# MCU.net
KiCad netlist of a schematic drawn in Altium Designer
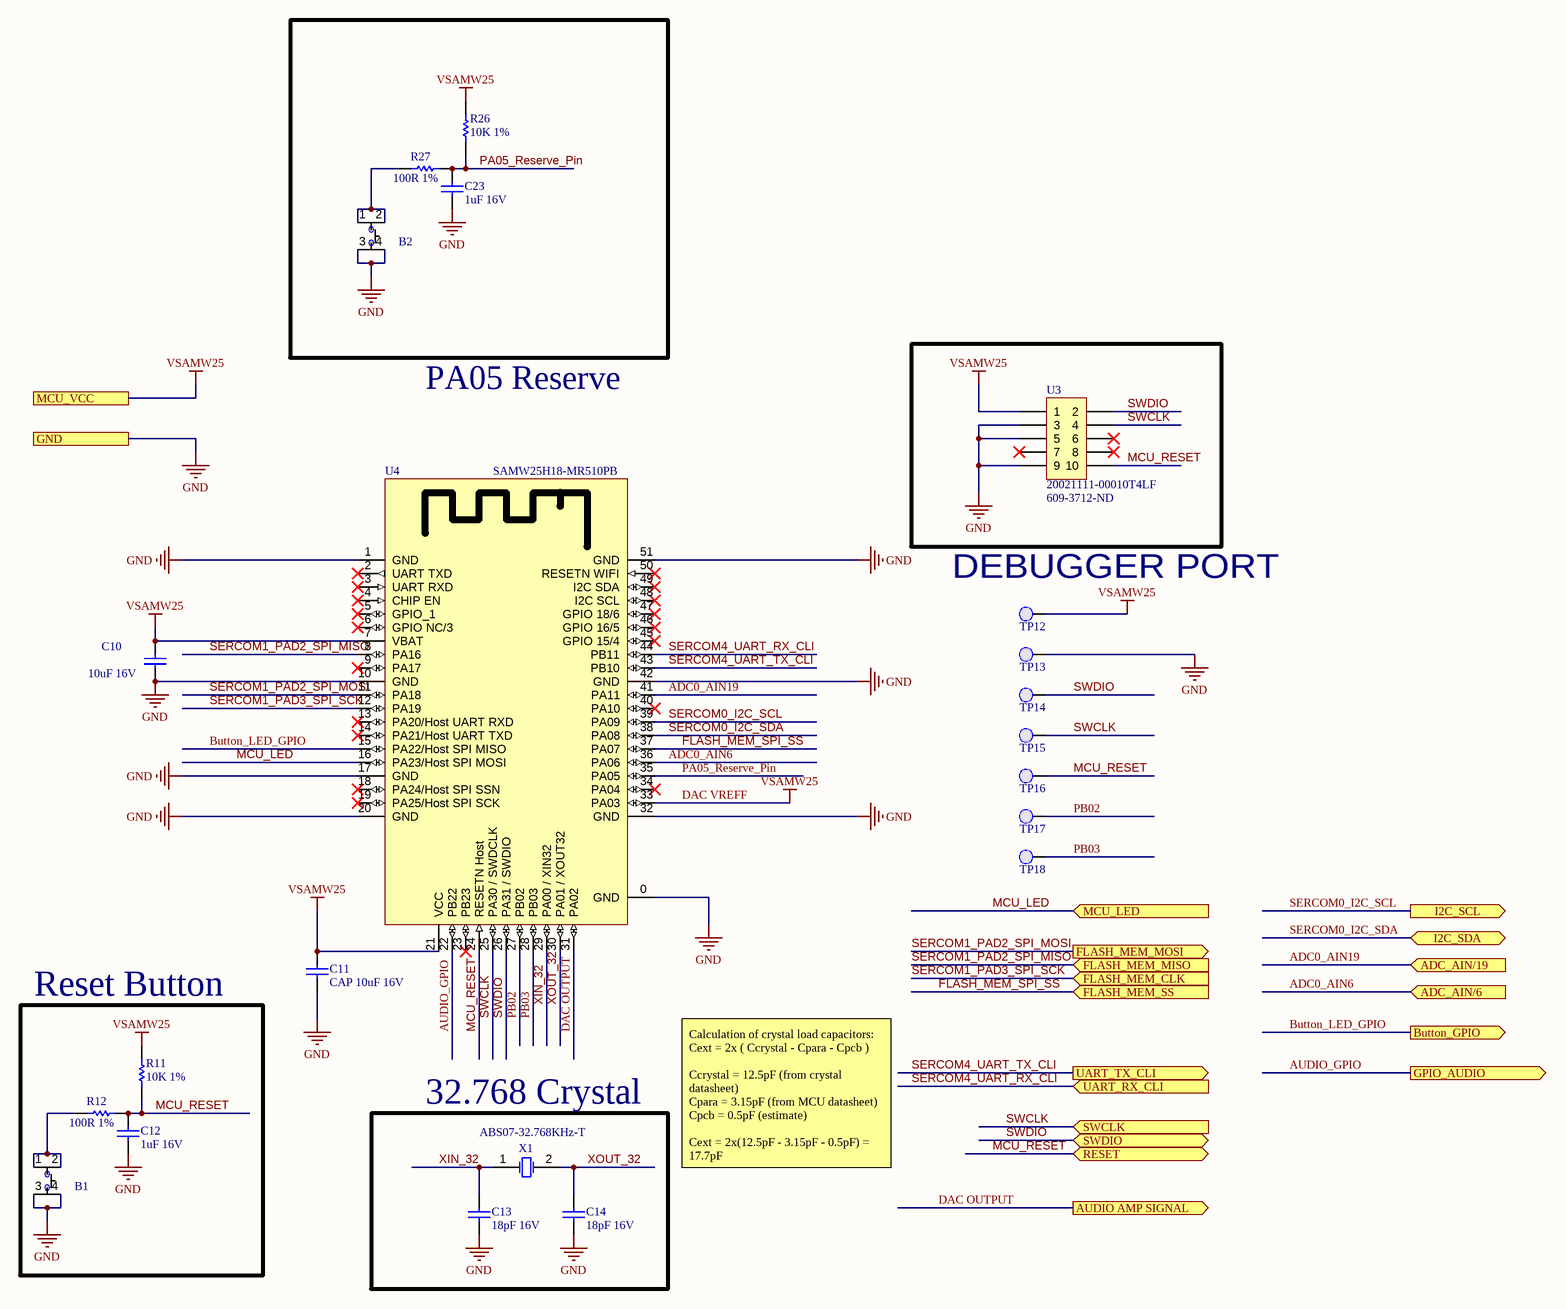
[diagram p0: MCU.SchDoc]

(export (version "E")
  (design (tool "Eeschema 10.0.6"))
  (components
    (comp (ref "B1")
      (value "PTS810 SJK 250 SMTR LFS")
      (footprint "PTS810 SJK 250 SMTR LFS")
      (description "SWITCH TACTILE SPST-NO 0.05A 16V Tactile Switch SPST-NO Top Actuated Surface Mount")
      (fields
        (field (name "MANUFACTURER") "ITT /  C&K Components")
        (field (name "MANUFACTURER PART NUMBER") "PTS810SJK250SMTRLFS")
      )
      (libsource (lib "Schematics") (part "PTS810 SJK 250 SMTR LFS"))
    )
    (comp (ref "B2")
      (value "PTS810 SJK 250 SMTR LFS")
      (footprint "PTS810 SJK 250 SMTR LFS")
      (description "SWITCH TACTILE SPST-NO 0.05A 16V Tactile Switch SPST-NO Top Actuated Surface Mount")
      (fields
        (field (name "MANUFACTURER") "ITT /  C&K Components")
        (field (name "MANUFACTURER PART NUMBER") "PTS810SJK250SMTRLFS")
      )
      (libsource (lib "Schematics") (part "PTS810 SJK 250 SMTR LFS"))
    )
    (comp (ref "C10")
      (value "10uF 16V")
      (footprint "CAPC0805(2012)145_N")
      (description "CAP 10uF 16V ±10% 0805 (2012 Metric) Thickness 1.45mm SMD")
      (fields (field (name "TOLERANCE") "Â±10%"))
      (libsource (lib "Altium Content Vault") (part "CAP"))
    )
    (comp (ref "C11")
      (value "CAP 10uF 16V")
      (footprint "CAPC0805(2012)145_N")
      (description "CAP 10uF 16V ±10% 0805 (2012 Metric) Thickness 1.45mm SMD")
      (fields (field (name "TOLERANCE") "Â±10%"))
      (libsource (lib "Altium Content Vault") (part "CAP"))
    )
    (comp (ref "C12")
      (value "1uF 16V")
      (footprint "CAPC0603(1608)100_N")
      (description "CAP 1uF 16V ±5% 0603 (1608 Metric) Thickness 1mm SMD")
      (fields (field (name "TOLERANCE") "Â±5%"))
      (libsource (lib "Altium Content Vault") (part "CAP"))
    )
    (comp (ref "C13")
      (value "18pF 16V")
      (footprint "CAPC0603(1608)100_N")
      (description "CAP 18pF 16V ±5% 0603 (1608 Metric) Thickness 1mm SMD")
      (fields (field (name "TOLERANCE") "Â±5%"))
      (libsource (lib "Altium Content Vault") (part "CAP"))
    )
    (comp (ref "C14")
      (value "18pF 16V")
      (footprint "CAPC0603(1608)100_N")
      (description "CAP 18pF 16V ±5% 0603 (1608 Metric) Thickness 1mm SMD")
      (fields (field (name "TOLERANCE") "Â±5%"))
      (libsource (lib "Altium Content Vault") (part "CAP"))
    )
    (comp (ref "C23")
      (value "1uF 16V")
      (footprint "CAPC0603(1608)100_N")
      (description "CAP 1uF 16V ±5% 0603 (1608 Metric) Thickness 1mm SMD")
      (fields (field (name "TOLERANCE") "Â±5%"))
      (libsource (lib "Altium Content Vault") (part "CAP"))
    )
    (comp (ref "R11")
      (value "10K 1%")
      (footprint "RESC0603(1608)_N")
      (description "10K 0.1W 1% 0603 (1608 Metric)  SMD")
      (fields (field (name "POWER") "0.1 W") (field (name "TOLERANCE") "1 %"))
      (libsource (lib "Altium Content Vault") (part "RES"))
    )
    (comp (ref "R12")
      (value "100R 1%")
      (footprint "RESC0603(1608)_N")
      (description "100R 0.1W 1% 0603 (1608 Metric)  SMD")
      (fields (field (name "TOLERANCE") "1 %") (field (name "POWER") "0.1 W"))
      (libsource (lib "Altium Content Vault") (part "RES"))
    )
    (comp (ref "R26")
      (value "10K 1%")
      (footprint "RESC0603(1608)_N")
      (description "10K 0.1W 1% 0603 (1608 Metric)  SMD")
      (fields (field (name "POWER") "0.1 W") (field (name "TOLERANCE") "1 %"))
      (libsource (lib "Altium Content Vault") (part "RES"))
    )
    (comp (ref "R27")
      (value "100R 1%")
      (footprint "RESC0603(1608)_N")
      (description "100R 0.1W 1% 0603 (1608 Metric)  SMD")
      (fields (field (name "TOLERANCE") "1 %") (field (name "POWER") "0.1 W"))
      (libsource (lib "Altium Content Vault") (part "RES"))
    )
    (comp (ref "TP12")
      (value "0.1\" Pad")
      (footprint "PCBComponent")
      (libsource (lib "Components - 12.02.20 - 18.05") (part "0.1{dblquote} Pad-A.4"))
    )
    (comp (ref "TP13")
      (value "0.1\" Pad")
      (footprint "PCBComponent")
      (libsource (lib "Components - 12.02.20 - 18.05") (part "0.1{dblquote} Pad-A.4"))
    )
    (comp (ref "TP14")
      (value "0.1\" Pad")
      (footprint "PCBComponent")
      (libsource (lib "Components - 12.02.20 - 18.05") (part "0.1{dblquote} Pad-A.4"))
    )
    (comp (ref "TP15")
      (value "0.1\" Pad")
      (footprint "PCBComponent")
      (libsource (lib "Components - 12.02.20 - 18.05") (part "0.1{dblquote} Pad-A.4"))
    )
    (comp (ref "TP16")
      (value "0.1\" Pad")
      (footprint "PCBComponent")
      (libsource (lib "Components - 12.02.20 - 18.05") (part "0.1{dblquote} Pad-A.4"))
    )
    (comp (ref "TP17")
      (value "0.1\" Pad")
      (footprint "PCBComponent")
      (libsource (lib "Components - 12.02.20 - 18.05") (part "0.1{dblquote} Pad-A.4"))
    )
    (comp (ref "TP18")
      (value "0.1\" Pad")
      (footprint "PCBComponent")
      (libsource (lib "Components - 12.02.20 - 18.05") (part "0.1{dblquote} Pad-A.4"))
    )
    (comp (ref "U3")
      (value "20021111-00010T4LF")
      (footprint "20021111-00010T4LF")
      (description "CONN HEADER 10POS UNSHD VERT T/H")
      (fields
        (field (name "MANUFACTURER") "Amphenol / FCI")
        (field (name "SUPPLIER PART NUMBER 1") "609-3712-ND")
      )
      (libsource (lib "Schematics") (part "20021111-00010T4LF"))
    )
    (comp (ref "U4")
      (value "SAMW25H18-MR510PB")
      (footprint "SAMW25H18-MR510PB")
      (description "RF TXRX MODULE WIFI TRACE ANT")
      (fields
        (field (name "MANUFACTURER") "Atmel")
        (field (name "MANUFACTURER PART NUMBER") "ATSAMW25H18-MR510PB")
      )
      (libsource (lib "Schematics") (part "SAMW25H18-MR510PB"))
    )
    (comp (ref "X1")
      (value "ABS07-32.768KHz-T")
      (footprint "ABRA-ABS07-2_V")
      (description "Crystal, 32.768 kHz, 12.5 pF, -40 to 85 degC, SMD Low Profile 3.2 x 1.5 x 0.9 mm, Tape and Reel")
      (fields (field (name "MANUFACTURER") "Abracon"))
      (libsource (lib "Altium Content Vault") (part "ABRA-ABS07-2"))
    )
  )
  (nets
    (net (code "1") (name "/ADC0_AIN6") (class "Default")
      (node (ref "U4") (pin "36") (pinfunction "PA06_36") (pintype "bidirectional"))
    )
    (net (code "2") (name "/ADC0_AIN19") (class "Default")
      (node (ref "U4") (pin "41") (pinfunction "PA11_41") (pintype "bidirectional"))
    )
    (net (code "3") (name "/AUDIO_GPIO") (class "Default")
      (node (ref "U4") (pin "22") (pinfunction "PB22_22") (pintype "bidirectional"))
    )
    (net (code "4") (name "/Button_LED_GPIO") (class "Default")
      (node (ref "U4") (pin "15") (pinfunction "PA22/Host_SPI_MISO_15") (pintype "bidirectional"))
    )
    (net (code "5") (name "/DAC OUTPUT") (class "Default")
      (node (ref "U4") (pin "31") (pinfunction "PA02_31") (pintype "bidirectional"))
    )
    (net (code "6") (name "/FLASH_MEM_SPI_SS") (class "Default")
      (node (ref "U4") (pin "37") (pinfunction "PA07_37") (pintype "bidirectional"))
    )
    (net (code "7") (name "/MCU_LED") (class "Default")
      (node (ref "U4") (pin "16") (pinfunction "PA23/Host_SPI_MOSI_16") (pintype "bidirectional"))
    )
    (net (code "8") (name "/MCU_RESET") (class "Default")
      (node (ref "C12") (pin "2") (pinfunction "2_2") (pintype "passive"))
      (node (ref "R11") (pin "1") (pinfunction "1_1") (pintype "passive"))
      (node (ref "R12") (pin "2") (pinfunction "2_2") (pintype "passive"))
      (node (ref "TP16") (pin "1") (pinfunction "PAD_1") (pintype "passive"))
      (node (ref "U3") (pin "10") (pinfunction "10_10") (pintype "passive"))
      (node (ref "U4") (pin "24") (pinfunction "RESETN_Host_24") (pintype "input"))
    )
    (net (code "9") (name "/PA05_Reserve_Pin") (class "Default")
      (node (ref "C23") (pin "2") (pinfunction "2_2") (pintype "passive"))
      (node (ref "R26") (pin "1") (pinfunction "1_1") (pintype "passive"))
      (node (ref "R27") (pin "2") (pinfunction "2_2") (pintype "passive"))
      (node (ref "U4") (pin "35") (pinfunction "PA05_35") (pintype "bidirectional"))
    )
    (net (code "10") (name "/PB02") (class "Default")
      (node (ref "TP17") (pin "1") (pinfunction "PAD_1") (pintype "passive"))
      (node (ref "U4") (pin "27") (pinfunction "PB02_27") (pintype "bidirectional"))
    )
    (net (code "11") (name "/PB03") (class "Default")
      (node (ref "TP18") (pin "1") (pinfunction "PAD_1") (pintype "passive"))
      (node (ref "U4") (pin "28") (pinfunction "PB03_28") (pintype "bidirectional"))
    )
    (net (code "12") (name "/SERCOM0_I2C_SCL") (class "Default")
      (node (ref "U4") (pin "39") (pinfunction "PA09_39") (pintype "bidirectional"))
    )
    (net (code "13") (name "/SERCOM0_I2C_SDA") (class "Default")
      (node (ref "U4") (pin "38") (pinfunction "PA08_38") (pintype "bidirectional"))
    )
    (net (code "14") (name "/SERCOM1_PAD2_SPI_MISO") (class "Default")
      (node (ref "U4") (pin "8") (pinfunction "PA16_8") (pintype "bidirectional"))
    )
    (net (code "15") (name "/SERCOM1_PAD2_SPI_MOSI") (class "Default")
      (node (ref "U4") (pin "11") (pinfunction "PA18_11") (pintype "bidirectional"))
    )
    (net (code "16") (name "/SERCOM1_PAD3_SPI_SCK") (class "Default")
      (node (ref "U4") (pin "12") (pinfunction "PA19_12") (pintype "bidirectional"))
    )
    (net (code "17") (name "/SERCOM4_UART_RX_CLI") (class "Default")
      (node (ref "U4") (pin "44") (pinfunction "PB11_44") (pintype "bidirectional"))
    )
    (net (code "18") (name "/SERCOM4_UART_TX_CLI") (class "Default")
      (node (ref "U4") (pin "43") (pinfunction "PB10_43") (pintype "bidirectional"))
    )
    (net (code "19") (name "/SWCLK") (class "Default")
      (node (ref "TP15") (pin "1") (pinfunction "PAD_1") (pintype "passive"))
      (node (ref "U3") (pin "4") (pinfunction "4_4") (pintype "passive"))
      (node (ref "U4") (pin "25") (pinfunction "PA30_/_SWDCLK_25") (pintype "bidirectional"))
    )
    (net (code "20") (name "/SWDIO") (class "Default")
      (node (ref "TP14") (pin "1") (pinfunction "PAD_1") (pintype "passive"))
      (node (ref "U3") (pin "2") (pinfunction "2_2") (pintype "passive"))
      (node (ref "U4") (pin "26") (pinfunction "PA31_/_SWDIO_26") (pintype "bidirectional"))
    )
    (net (code "21") (name "/XIN_32") (class "Default")
      (node (ref "C13") (pin "2") (pinfunction "2_2") (pintype "passive"))
      (node (ref "U4") (pin "29") (pinfunction "PA00_/_XIN32_29") (pintype "bidirectional"))
      (node (ref "X1") (pin "1") (pinfunction "X1_1") (pintype "passive"))
    )
    (net (code "22") (name "/XOUT_32") (class "Default")
      (node (ref "C14") (pin "2") (pinfunction "2_2") (pintype "passive"))
      (node (ref "U4") (pin "30") (pinfunction "PA01_/_XOUT32_30") (pintype "bidirectional"))
      (node (ref "X1") (pin "2") (pinfunction "X2_2") (pintype "passive"))
    )
    (net (code "23") (name "GND") (class "Default")
      (node (ref "B1") (pin "3") (pinfunction "3_3") (pintype "power_in"))
      (node (ref "B1") (pin "4") (pinfunction "4_4") (pintype "power_in"))
      (node (ref "B2") (pin "3") (pinfunction "3_3") (pintype "power_in"))
      (node (ref "B2") (pin "4") (pinfunction "4_4") (pintype "power_in"))
      (node (ref "C10") (pin "1") (pinfunction "1_1") (pintype "passive"))
      (node (ref "C11") (pin "1") (pinfunction "1_1") (pintype "passive"))
      (node (ref "C12") (pin "1") (pinfunction "1_1") (pintype "passive"))
      (node (ref "C13") (pin "1") (pinfunction "1_1") (pintype "passive"))
      (node (ref "C14") (pin "1") (pinfunction "1_1") (pintype "passive"))
      (node (ref "C23") (pin "1") (pinfunction "1_1") (pintype "passive"))
      (node (ref "TP13") (pin "1") (pinfunction "PAD_1") (pintype "passive"))
      (node (ref "U3") (pin "3") (pinfunction "3_3") (pintype "passive"))
      (node (ref "U3") (pin "5") (pinfunction "5_5") (pintype "passive"))
      (node (ref "U3") (pin "9") (pinfunction "9_9") (pintype "passive"))
      (node (ref "U4") (pin "0") (pinfunction "GND_0") (pintype "power_in"))
      (node (ref "U4") (pin "1") (pinfunction "GND_1") (pintype "power_in"))
      (node (ref "U4") (pin "10") (pinfunction "GND_10") (pintype "power_in"))
      (node (ref "U4") (pin "17") (pinfunction "GND_17") (pintype "power_in"))
      (node (ref "U4") (pin "20") (pinfunction "GND_20") (pintype "power_in"))
      (node (ref "U4") (pin "32") (pinfunction "GND_32") (pintype "power_in"))
      (node (ref "U4") (pin "42") (pinfunction "GND_42") (pintype "power_in"))
      (node (ref "U4") (pin "51") (pinfunction "GND_51") (pintype "power_in"))
    )
    (net (code "24") (name "Net-(B1-Pad1)") (class "Default")
      (node (ref "B1") (pin "1") (pinfunction "1_1") (pintype "power_in"))
      (node (ref "B1") (pin "2") (pinfunction "2_2") (pintype "power_in"))
      (node (ref "R12") (pin "1") (pinfunction "1_1") (pintype "passive"))
    )
    (net (code "25") (name "Net-(B2-Pad1)") (class "Default")
      (node (ref "B2") (pin "1") (pinfunction "1_1") (pintype "power_in"))
      (node (ref "B2") (pin "2") (pinfunction "2_2") (pintype "power_in"))
      (node (ref "R27") (pin "1") (pinfunction "1_1") (pintype "passive"))
    )
    (net (code "26") (name "VSAMW25") (class "Default")
      (node (ref "C10") (pin "2") (pinfunction "2_2") (pintype "passive"))
      (node (ref "C11") (pin "2") (pinfunction "2_2") (pintype "passive"))
      (node (ref "R11") (pin "2") (pinfunction "2_2") (pintype "passive"))
      (node (ref "R26") (pin "2") (pinfunction "2_2") (pintype "passive"))
      (node (ref "TP12") (pin "1") (pinfunction "PAD_1") (pintype "passive"))
      (node (ref "U3") (pin "1") (pinfunction "1_1") (pintype "passive"))
      (node (ref "U4") (pin "21") (pinfunction "VCC_21") (pintype "power_in"))
      (node (ref "U4") (pin "33") (pinfunction "PA03_33") (pintype "bidirectional"))
      (node (ref "U4") (pin "7") (pinfunction "VBAT_7") (pintype "power_in"))
    )
    (net (code "27") (name "unconnected-(U3-Pad6)") (class "Default")
      (node (ref "U3") (pin "6") (pinfunction "6_6") (pintype "passive+no_connect"))
    )
    (net (code "28") (name "unconnected-(U3-Pad7)") (class "Default")
      (node (ref "U3") (pin "7") (pinfunction "7_7") (pintype "passive+no_connect"))
    )
    (net (code "29") (name "unconnected-(U3-Pad8)") (class "Default")
      (node (ref "U3") (pin "8") (pinfunction "8_8") (pintype "passive+no_connect"))
    )
    (net (code "30") (name "unconnected-(U4-CHIP_EN-Pad4)") (class "Default")
      (node (ref "U4") (pin "4") (pinfunction "CHIP_EN_4") (pintype "input+no_connect"))
    )
    (net (code "31") (name "unconnected-(U4-GPIO_1-Pad5)") (class "Default")
      (node (ref "U4") (pin "5") (pinfunction "GPIO_1_5") (pintype "bidirectional+no_connect"))
    )
    (net (code "32") (name "unconnected-(U4-GPIO_15{slash}4-Pad45)") (class "Default")
      (node (ref "U4") (pin "45") (pinfunction "GPIO_15/4_45") (pintype "bidirectional+no_connect"))
    )
    (net (code "33") (name "unconnected-(U4-GPIO_16{slash}5-Pad46)") (class "Default")
      (node (ref "U4") (pin "46") (pinfunction "GPIO_16/5_46") (pintype "bidirectional+no_connect"))
    )
    (net (code "34") (name "unconnected-(U4-GPIO_18{slash}6-Pad47)") (class "Default")
      (node (ref "U4") (pin "47") (pinfunction "GPIO_18/6_47") (pintype "bidirectional+no_connect"))
    )
    (net (code "35") (name "unconnected-(U4-GPIO_NC{slash}3-Pad6)") (class "Default")
      (node (ref "U4") (pin "6") (pinfunction "GPIO_NC/3_6") (pintype "bidirectional+no_connect"))
    )
    (net (code "36") (name "unconnected-(U4-I2C_SCL-Pad48)") (class "Default")
      (node (ref "U4") (pin "48") (pinfunction "I2C_SCL_48") (pintype "bidirectional+no_connect"))
    )
    (net (code "37") (name "unconnected-(U4-I2C_SDA-Pad49)") (class "Default")
      (node (ref "U4") (pin "49") (pinfunction "I2C_SDA_49") (pintype "bidirectional+no_connect"))
    )
    (net (code "38") (name "unconnected-(U4-PA04-Pad34)") (class "Default")
      (node (ref "U4") (pin "34") (pinfunction "PA04_34") (pintype "bidirectional+no_connect"))
    )
    (net (code "39") (name "unconnected-(U4-PA10-Pad40)") (class "Default")
      (node (ref "U4") (pin "40") (pinfunction "PA10_40") (pintype "bidirectional+no_connect"))
    )
    (net (code "40") (name "unconnected-(U4-PA17-Pad9)") (class "Default")
      (node (ref "U4") (pin "9") (pinfunction "PA17_9") (pintype "bidirectional+no_connect"))
    )
    (net (code "41") (name "unconnected-(U4-PA20{slash}Host_UART_RXD-Pad13)") (class "Default")
      (node (ref "U4") (pin "13") (pinfunction "PA20/Host_UART_RXD_13") (pintype "bidirectional+no_connect"))
    )
    (net (code "42") (name "unconnected-(U4-PA21{slash}Host_UART_TXD-Pad14)") (class "Default")
      (node (ref "U4") (pin "14") (pinfunction "PA21/Host_UART_TXD_14") (pintype "bidirectional+no_connect"))
    )
    (net (code "43") (name "unconnected-(U4-PA24{slash}Host_SPI_SSN-Pad18)") (class "Default")
      (node (ref "U4") (pin "18") (pinfunction "PA24/Host_SPI_SSN_18") (pintype "bidirectional+no_connect"))
    )
    (net (code "44") (name "unconnected-(U4-PA25{slash}Host_SPI_SCK-Pad19)") (class "Default")
      (node (ref "U4") (pin "19") (pinfunction "PA25/Host_SPI_SCK_19") (pintype "bidirectional+no_connect"))
    )
    (net (code "45") (name "unconnected-(U4-PB23-Pad23)") (class "Default")
      (node (ref "U4") (pin "23") (pinfunction "PB23_23") (pintype "bidirectional+no_connect"))
    )
    (net (code "46") (name "unconnected-(U4-RESETN_WIFI-Pad50)") (class "Default")
      (node (ref "U4") (pin "50") (pinfunction "RESETN_WIFI_50") (pintype "input+no_connect"))
    )
    (net (code "47") (name "unconnected-(U4-UART_RXD-Pad3)") (class "Default")
      (node (ref "U4") (pin "3") (pinfunction "UART_RXD_3") (pintype "input+no_connect"))
    )
    (net (code "48") (name "unconnected-(U4-UART_TXD-Pad2)") (class "Default")
      (node (ref "U4") (pin "2") (pinfunction "UART_TXD_2") (pintype "output+no_connect"))
    )
  )
)
